# rc-light-controller-ws2812-12f1840.net
KiCad netlist of a schematic drawn in EAGLE
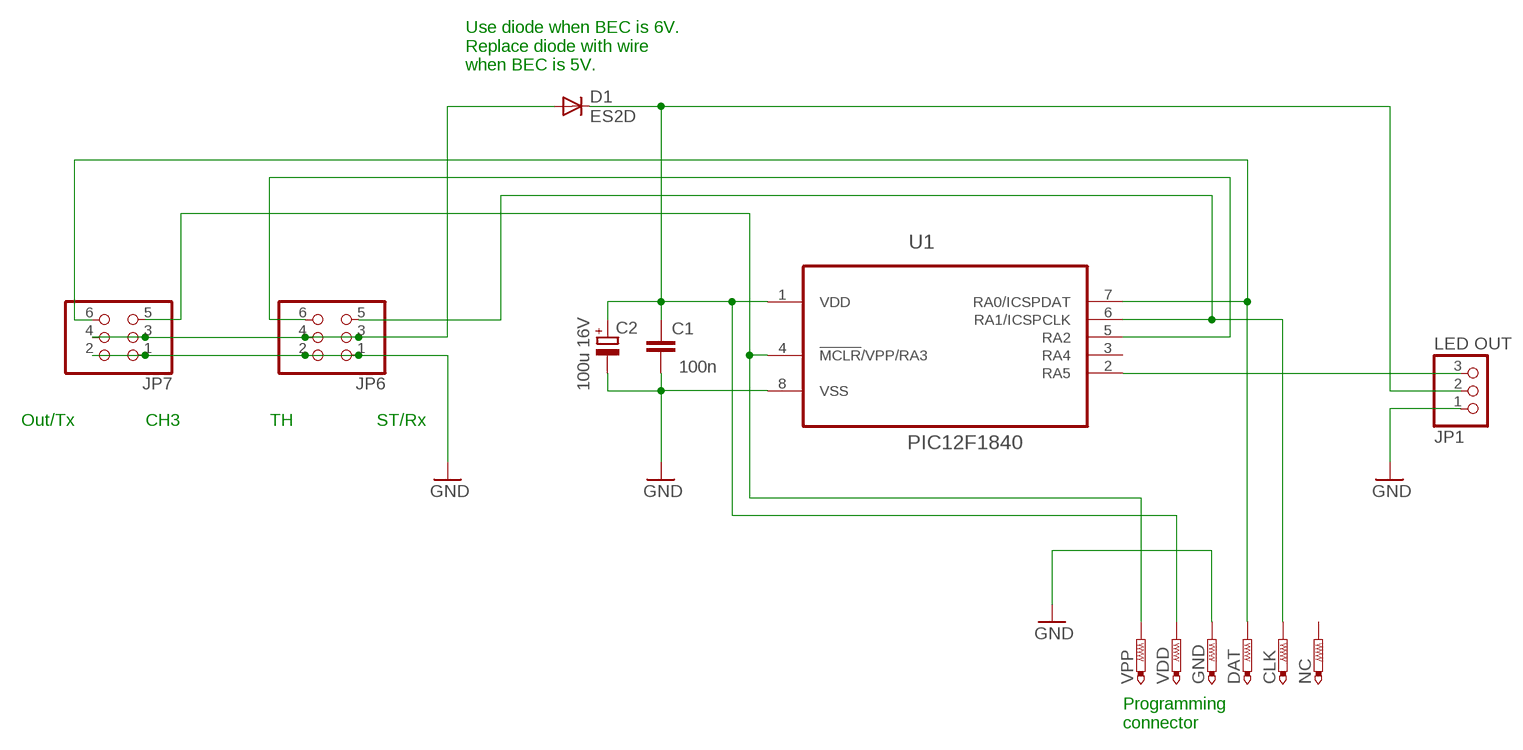
[diagram p0: schematic, sheet 1]

(export (version "E")
  (design (tool "Eeschema 10.0.6"))
  (components
    (comp (ref "C1")
      (value "100n")
      (footprint "eagle-import:C0805K")
      (libsource (lib "eagle-import") (part "C-EUC0805K"))
    )
    (comp (ref "C2")
      (value "100u 16V")
      (footprint "eagle-import:153CLV-0605")
      (libsource (lib "eagle-import") (part "CPOL-EU153CLV-0605"))
    )
    (comp (ref "CLK")
      (value "PTR1TP14R")
      (footprint "eagle-import:TP14R")
      (libsource (lib "eagle-import") (part "PTR1TP14R"))
    )
    (comp (ref "D1")
      (value "ES2D")
      (footprint "eagle-import:SMB")
      (libsource (lib "eagle-import") (part "ES2D"))
    )
    (comp (ref "DAT")
      (value "PTR1TP14R")
      (footprint "eagle-import:TP14R")
      (libsource (lib "eagle-import") (part "PTR1TP14R"))
    )
    (comp (ref "GND")
      (value "PTR1TP14R")
      (footprint "eagle-import:TP14R")
      (libsource (lib "eagle-import") (part "PTR1TP14R"))
    )
    (comp (ref "JP1")
      (value "LED OUT")
      (footprint "eagle-import:1X03")
      (libsource (lib "eagle-import") (part "PINHD-1X3"))
    )
    (comp (ref "JP6")
      (value "PINHD-2X3")
      (footprint "eagle-import:2X03")
      (libsource (lib "eagle-import") (part "PINHD-2X3"))
    )
    (comp (ref "JP7")
      (value "PINHD-2X3")
      (footprint "eagle-import:2X03")
      (libsource (lib "eagle-import") (part "PINHD-2X3"))
    )
    (comp (ref "NC")
      (value "PTR1TP14R")
      (footprint "eagle-import:TP14R")
      (libsource (lib "eagle-import") (part "PTR1TP14R"))
    )
    (comp (ref "U1")
      (value "12F1840")
      (footprint "eagle-import:SOIC127P600X175-8N")
      (fields (field (name "MPN") "PIC12F1840-E/SN"))
      (libsource (lib "eagle-import") (part "PIC12F1840-E/SN"))
    )
    (comp (ref "VDD")
      (value "PTR1TP14R")
      (footprint "eagle-import:TP14R")
      (libsource (lib "eagle-import") (part "PTR1TP14R"))
    )
    (comp (ref "VPP")
      (value "PTR1TP14SQ")
      (footprint "eagle-import:TP14SQ")
      (libsource (lib "eagle-import") (part "PTR1TP14SQ"))
    )
  )
  (nets
    (net (code "1") (name "GND") (class "Default")
      (node (ref "C1") (pin "2") (pinfunction "2_2") (pintype "passive"))
      (node (ref "C2") (pin "-") (pinfunction "-_-") (pintype "passive"))
      (node (ref "GND") (pin "TP") (pinfunction "TP_TP") (pintype "input"))
      (node (ref "JP1") (pin "1") (pinfunction "1_1") (pintype "passive"))
      (node (ref "JP6") (pin "1") (pinfunction "1_1") (pintype "passive"))
      (node (ref "JP6") (pin "2") (pinfunction "2_2") (pintype "passive"))
      (node (ref "JP7") (pin "1") (pinfunction "1_1") (pintype "passive"))
      (node (ref "JP7") (pin "2") (pinfunction "2_2") (pintype "passive"))
      (node (ref "U1") (pin "8") (pinfunction "VSS_8") (pintype "power_in"))
    )
    (net (code "2") (name "Net-(D1-PadA)") (class "Default")
      (node (ref "D1") (pin "A") (pinfunction "A_A") (pintype "passive"))
      (node (ref "JP6") (pin "3") (pinfunction "3_3") (pintype "passive"))
      (node (ref "JP6") (pin "4") (pinfunction "4_4") (pintype "passive"))
      (node (ref "JP7") (pin "3") (pinfunction "3_3") (pintype "passive"))
      (node (ref "JP7") (pin "4") (pinfunction "4_4") (pintype "passive"))
    )
    (net (code "3") (name "Net-(U1-RA0{slash}ICSPDAT)") (class "Default")
      (node (ref "DAT") (pin "TP") (pinfunction "TP_TP") (pintype "input"))
      (node (ref "JP7") (pin "6") (pinfunction "6_6") (pintype "passive"))
      (node (ref "U1") (pin "7") (pinfunction "RA0/ICSPDAT_7") (pintype "bidirectional"))
    )
    (net (code "4") (name "Net-(U1-RA1{slash}ICSPCLK)") (class "Default")
      (node (ref "CLK") (pin "TP") (pinfunction "TP_TP") (pintype "input"))
      (node (ref "JP6") (pin "5") (pinfunction "5_5") (pintype "passive"))
      (node (ref "U1") (pin "6") (pinfunction "RA1/ICSPCLK_6") (pintype "bidirectional"))
    )
    (net (code "5") (name "Net-(U1-RA2)") (class "Default")
      (node (ref "JP6") (pin "6") (pinfunction "6_6") (pintype "passive"))
      (node (ref "U1") (pin "5") (pinfunction "RA2_5") (pintype "bidirectional"))
    )
    (net (code "6") (name "Net-(U1-RA5)") (class "Default")
      (node (ref "JP1") (pin "3") (pinfunction "3_3") (pintype "passive"))
      (node (ref "U1") (pin "2") (pinfunction "RA5_2") (pintype "bidirectional"))
    )
    (net (code "7") (name "Net-(U1-VDD)") (class "Default")
      (node (ref "C1") (pin "1") (pinfunction "1_1") (pintype "passive"))
      (node (ref "C2") (pin "+") (pinfunction "+_+") (pintype "passive"))
      (node (ref "D1") (pin "C") (pinfunction "C_C") (pintype "passive"))
      (node (ref "JP1") (pin "2") (pinfunction "2_2") (pintype "passive"))
      (node (ref "U1") (pin "1") (pinfunction "VDD_1") (pintype "power_in"))
      (node (ref "VDD") (pin "TP") (pinfunction "TP_TP") (pintype "input"))
    )
    (net (code "8") (name "Net-(U1-~{MCLR}{slash}VPP{slash}RA3)") (class "Default")
      (node (ref "JP7") (pin "5") (pinfunction "5_5") (pintype "passive"))
      (node (ref "U1") (pin "4") (pinfunction "~{MCLR}/VPP/RA3_4") (pintype "input"))
      (node (ref "VPP") (pin "TP") (pinfunction "TP_TP") (pintype "input"))
    )
    (net (code "9") (name "unconnected-(NC-PadTP)") (class "Default")
      (node (ref "NC") (pin "TP") (pinfunction "TP_TP") (pintype "input"))
    )
    (net (code "10") (name "unconnected-(U1-RA4-Pad3)") (class "Default")
      (node (ref "U1") (pin "3") (pinfunction "RA4_3") (pintype "bidirectional"))
    )
  )
)
